# MagnetismLock.net
KiCad netlist of a schematic drawn in Altium Designer
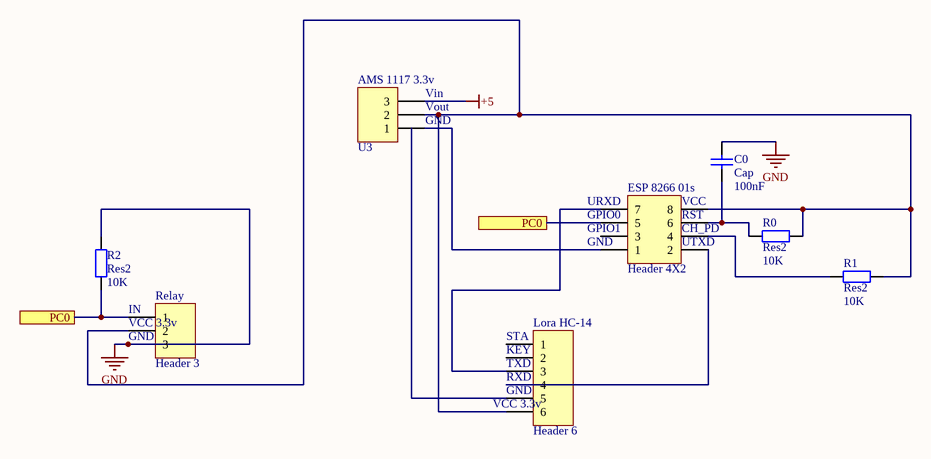
[diagram p0: MagnetismLock.SchDoc]

(export (version "E")
  (design (tool "Eeschema 10.0.6"))
  (components
    (comp (ref "AMS 1117 3.3v")
      (value "U3")
      (footprint "HDR1X3")
      (description "Header, 3-Pin")
      (fields (field (name "PUBLISHER") "Altium Limited"))
      (libsource (lib "") (part "Header 3_1"))
    )
    (comp (ref "C0")
      (value "Cap")
      (footprint "RAD-0.3")
      (description "Capacitor")
      (fields (field (name "ALTIUM_VALUE") "100nF") (field (name "PUBLISHER") "Altium Limited"))
      (libsource (lib "Miscellaneous Devices") (part "Cap"))
    )
    (comp (ref "ESP 8266 01s")
      (value "Header 4X2")
      (footprint "HDR2X4")
      (description "Header, 4-Pin, Dual row")
      (fields (field (name "PUBLISHER") "Altium Limited"))
      (libsource (lib "Miscellaneous Connectors") (part "Header 4X2"))
    )
    (comp (ref "Lora HC-14")
      (value "Header 6")
      (footprint "HDR1X6")
      (description "Header, 6-Pin")
      (fields (field (name "PUBLISHER") "Altium Limited"))
      (libsource (lib "Miscellaneous Connectors") (part "Header 6"))
    )
    (comp (ref "R0")
      (value "Res2")
      (footprint "AXIAL-0.4")
      (description "Resistor")
      (fields (field (name "ALTIUM_VALUE") "10K") (field (name "PUBLISHER") "Altium Limited"))
      (libsource (lib "Miscellaneous Devices") (part "Res2"))
    )
    (comp (ref "R1")
      (value "Res2")
      (footprint "AXIAL-0.4")
      (description "Resistor")
      (fields (field (name "ALTIUM_VALUE") "10K") (field (name "PUBLISHER") "Altium Limited"))
      (libsource (lib "Miscellaneous Devices") (part "Res2"))
    )
    (comp (ref "R2")
      (value "Res2")
      (footprint "AXIAL-0.4")
      (description "Resistor")
      (fields (field (name "ALTIUM_VALUE") "10K") (field (name "PUBLISHER") "Altium Limited"))
      (libsource (lib "") (part "Res2_1"))
    )
    (comp (ref "Relay")
      (value "Header 3")
      (footprint "HDR1X3")
      (description "Header, 3-Pin")
      (fields (field (name "PUBLISHER") "Altium Limited"))
      (libsource (lib "Miscellaneous Connectors") (part "Header 3"))
    )
  )
  (nets
    (net (code "1") (name "+5") (class "Default")
      (node (ref "AMS 1117 3.3v") (pin "3") (pinfunction "3_3") (pintype "passive"))
    )
    (net (code "2") (name "/PC0") (class "Default")
      (node (ref "ESP 8266 01s") (pin "5") (pinfunction "5_5") (pintype "passive"))
      (node (ref "R2") (pin "2") (pinfunction "2_2") (pintype "passive"))
      (node (ref "Relay") (pin "1") (pinfunction "1_1") (pintype "passive"))
    )
    (net (code "3") (name "GND") (class "Default")
      (node (ref "C0") (pin "2") (pinfunction "2_2") (pintype "passive"))
      (node (ref "R2") (pin "1") (pinfunction "1_1") (pintype "passive"))
      (node (ref "Relay") (pin "3") (pinfunction "3_3") (pintype "passive"))
    )
    (net (code "4") (name "Net-(AMS 1117 3.3v-Pad1)") (class "Default")
      (node (ref "AMS 1117 3.3v") (pin "1") (pinfunction "1_1") (pintype "passive"))
      (node (ref "ESP 8266 01s") (pin "1") (pinfunction "1_1") (pintype "passive"))
    )
    (net (code "5") (name "Net-(AMS 1117 3.3v-Pad2)") (class "Default")
      (node (ref "AMS 1117 3.3v") (pin "2") (pinfunction "2_2") (pintype "passive"))
      (node (ref "ESP 8266 01s") (pin "8") (pinfunction "8_8") (pintype "passive"))
      (node (ref "Lora HC-14") (pin "6") (pinfunction "6_6") (pintype "passive"))
      (node (ref "R0") (pin "1") (pinfunction "1_1") (pintype "passive"))
      (node (ref "R1") (pin "1") (pinfunction "1_1") (pintype "passive"))
      (node (ref "Relay") (pin "2") (pinfunction "2_2") (pintype "passive"))
    )
    (net (code "6") (name "Net-(C0-Pad1)") (class "Default")
      (node (ref "C0") (pin "1") (pinfunction "1_1") (pintype "passive"))
      (node (ref "ESP 8266 01s") (pin "6") (pinfunction "6_6") (pintype "passive"))
      (node (ref "R0") (pin "2") (pinfunction "2_2") (pintype "passive"))
    )
    (net (code "7") (name "Net-(ESP 8266 01s-Pad2)") (class "Default")
      (node (ref "ESP 8266 01s") (pin "2") (pinfunction "2_2") (pintype "passive"))
      (node (ref "Lora HC-14") (pin "4") (pinfunction "4_4") (pintype "passive"))
    )
    (net (code "8") (name "Net-(ESP 8266 01s-Pad4)") (class "Default")
      (node (ref "ESP 8266 01s") (pin "4") (pinfunction "4_4") (pintype "passive"))
      (node (ref "R1") (pin "2") (pinfunction "2_2") (pintype "passive"))
    )
    (net (code "9") (name "Net-(ESP 8266 01s-Pad7)") (class "Default")
      (node (ref "ESP 8266 01s") (pin "7") (pinfunction "7_7") (pintype "passive"))
      (node (ref "Lora HC-14") (pin "3") (pinfunction "3_3") (pintype "passive"))
    )
    (net (code "10") (name "unconnected-(ESP 8266 01s-Pad3)") (class "Default")
      (node (ref "ESP 8266 01s") (pin "3") (pinfunction "3_3") (pintype "passive"))
    )
    (net (code "11") (name "unconnected-(Lora HC-14-Pad1)") (class "Default")
      (node (ref "Lora HC-14") (pin "1") (pinfunction "1_1") (pintype "passive"))
    )
    (net (code "12") (name "unconnected-(Lora HC-14-Pad2)") (class "Default")
      (node (ref "Lora HC-14") (pin "2") (pinfunction "2_2") (pintype "passive"))
    )
    (net (code "13") (name "unconnected-(Lora HC-14-Pad5)") (class "Default")
      (node (ref "Lora HC-14") (pin "5") (pinfunction "5_5") (pintype "passive"))
    )
  )
)
